# SCH_Color_Sensor_OPS_2021-07-07.net
KiCad netlist of a schematic drawn in EasyEDA
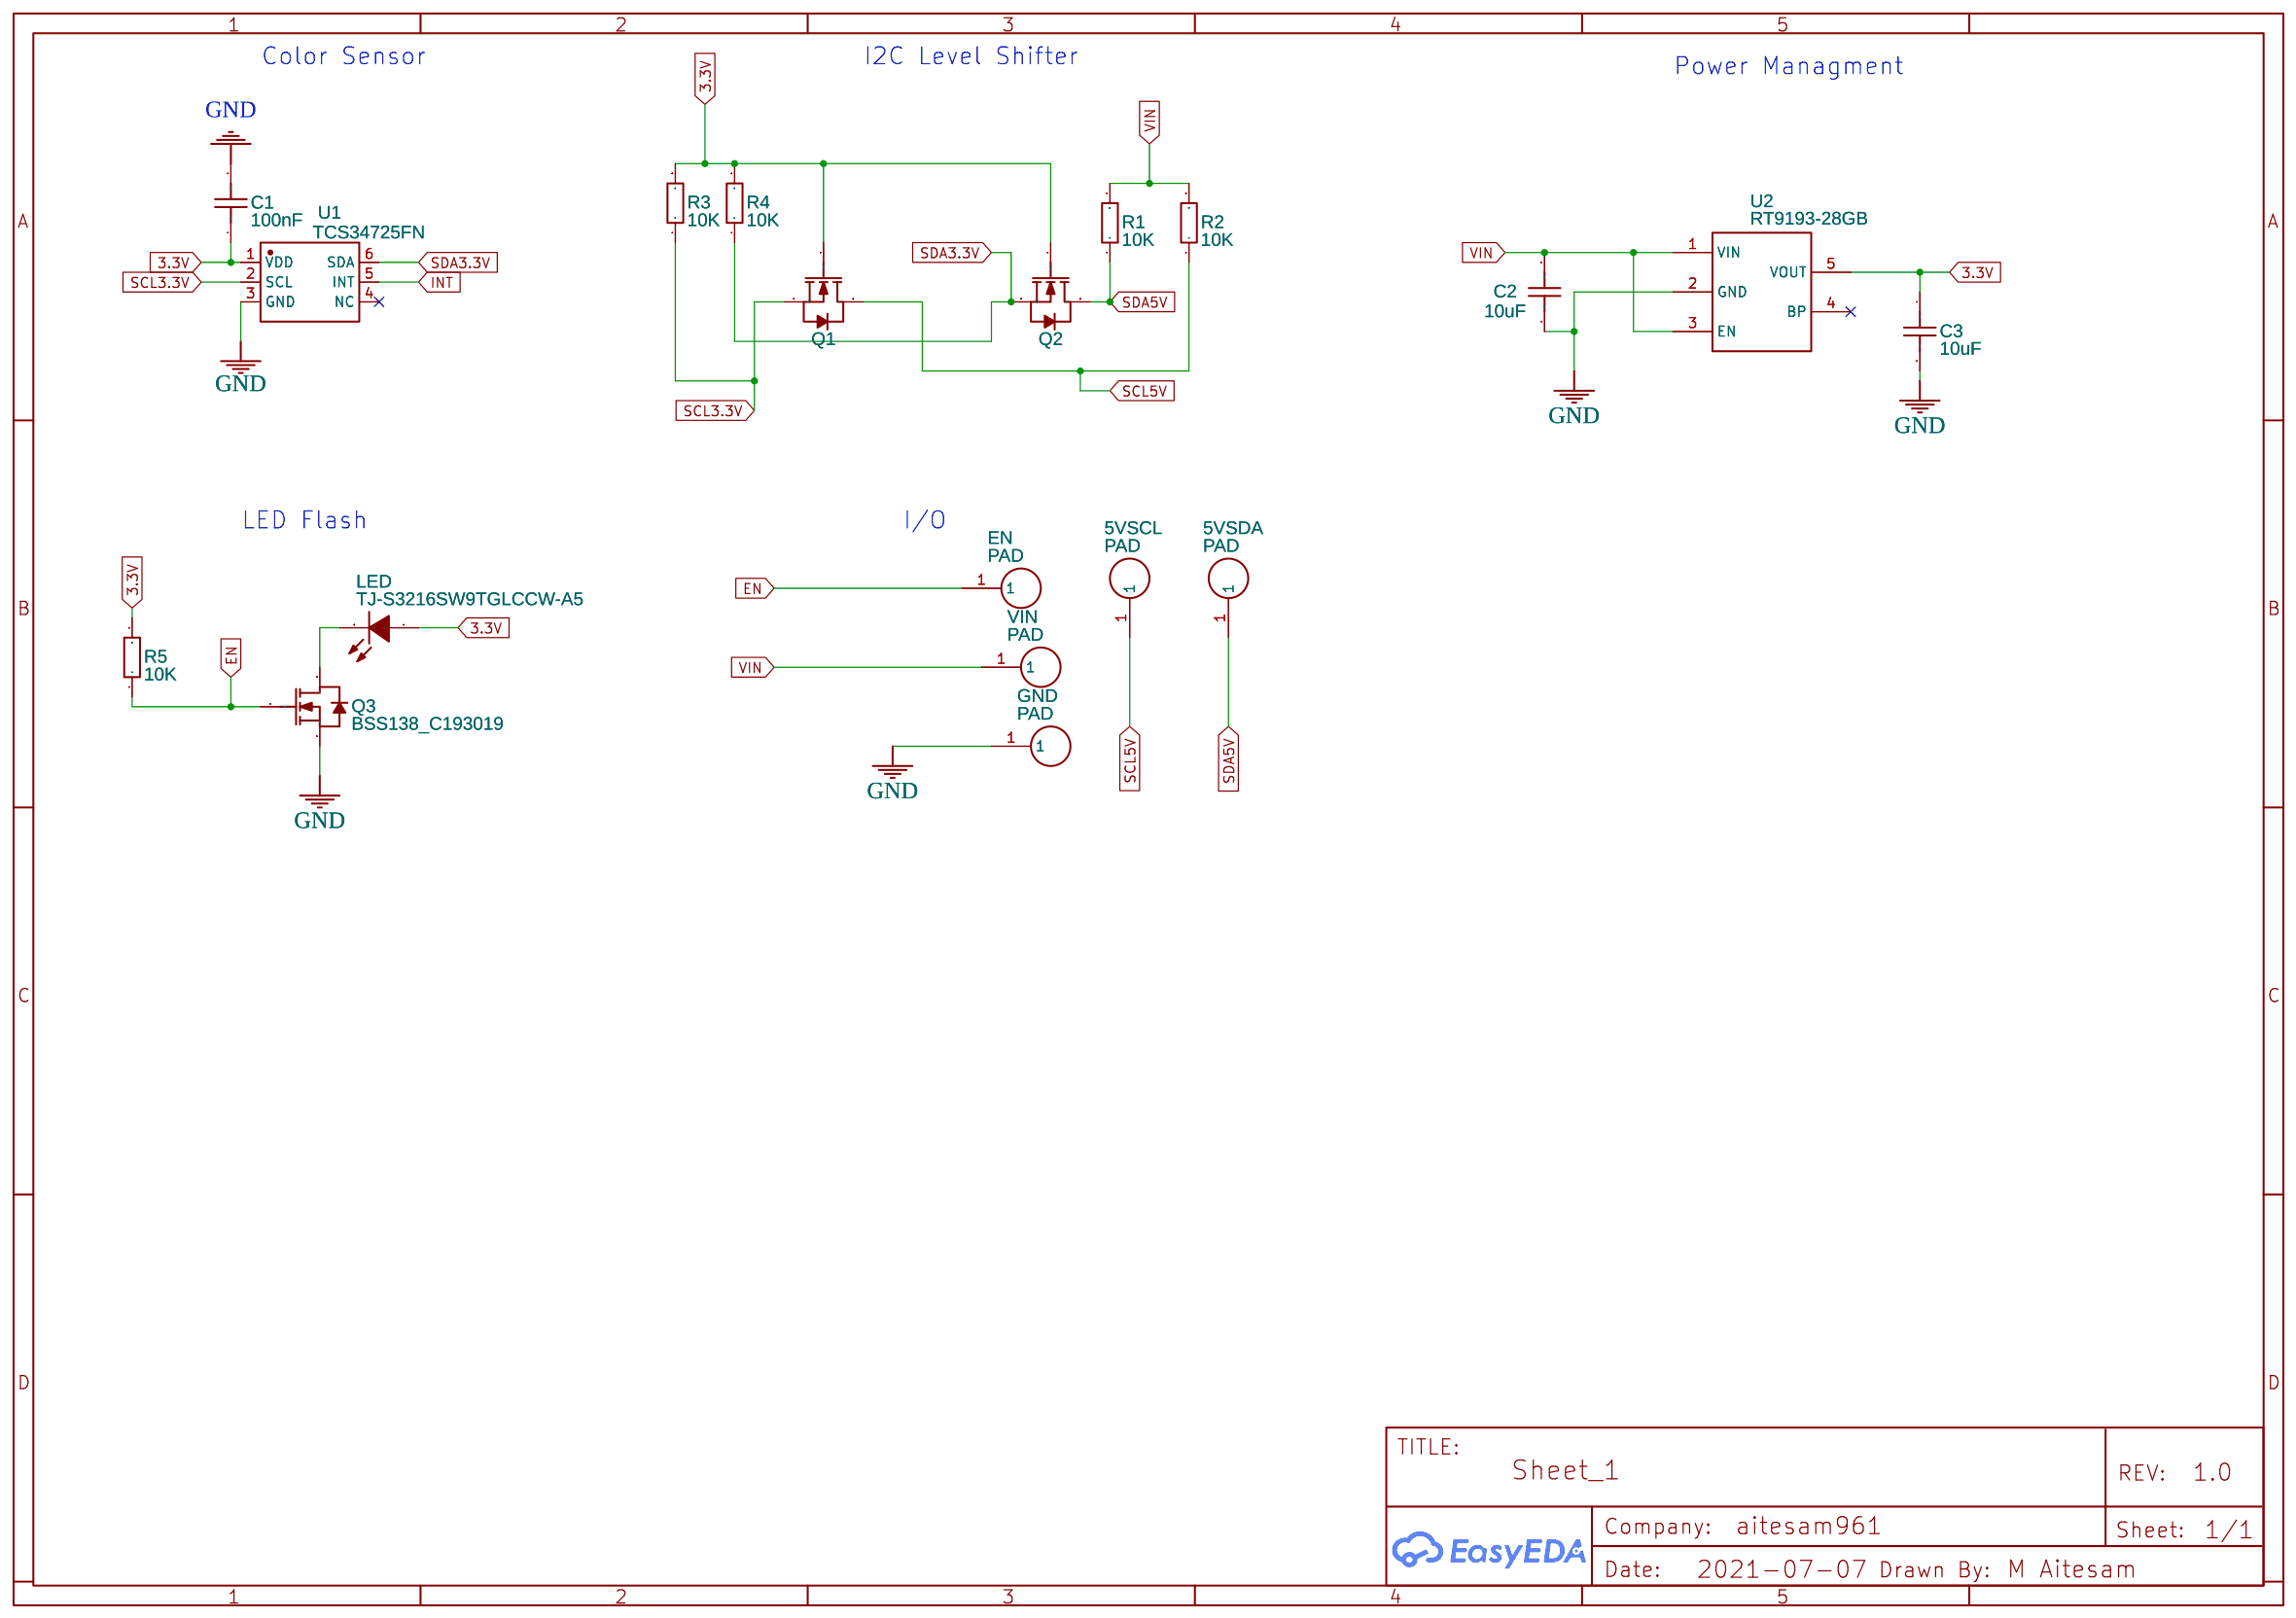
[diagram p0: schematic sheet]

(export (version "E")
  (design (tool "Eeschema 10.0.6"))
  (components
    (comp (ref "5VSCL") (value "PAD") (libsource (lib "") (part "PAD_2")))
    (comp (ref "5VSDA") (value "PAD") (libsource (lib "") (part "PAD_3")))
    (comp (ref "C1")
      (value "100nF")
      (fields
        (field (name "BOM_Manufacturer Part") "GCM155R71C104KA55D")
        (field (name "BOM_Supplier Part") "C85857")
      )
      (libsource (lib "") (part "GCM155R71C104KA55D"))
    )
    (comp (ref "C2")
      (value "10uF")
      (fields
        (field (name "BOM_Manufacturer Part") "CL10A106MQ8NNNC")
        (field (name "BOM_Supplier Part") "C1691")
      )
      (libsource (lib "") (part "CL10A106MQ8NNNC_1"))
    )
    (comp (ref "C3")
      (value "10uF")
      (fields
        (field (name "BOM_Manufacturer Part") "CL10A106MQ8NNNC")
        (field (name "BOM_Supplier Part") "C1691")
      )
      (libsource (lib "") (part "CL10A106MQ8NNNC"))
    )
    (comp (ref "EN") (value "PAD") (libsource (lib "") (part "PAD_4")))
    (comp (ref "GND") (value "PAD") (libsource (lib "") (part "PAD_1")))
    (comp (ref "LED")
      (value "TJ-S3216SW9TGLCCW-A5")
      (fields (field (name "BOM_Supplier Part") "C192680"))
      (libsource (lib "") (part "TJ-S3216SW9TGLCCW-A5"))
    )
    (comp (ref "Q1")
      (value "BSS138_C193019")
      (fields (field (name "BOM_Manufacturer Part") "BSS138") (field (name "BOM_Supplier Part") "C193019"))
      (libsource (lib "") (part "BSS138_C193019_1"))
    )
    (comp (ref "Q2")
      (value "BSS138_C193019")
      (fields (field (name "BOM_Manufacturer Part") "BSS138") (field (name "BOM_Supplier Part") "C193019"))
      (libsource (lib "") (part "BSS138_C193019_1"))
    )
    (comp (ref "Q3")
      (value "BSS138_C193019")
      (fields (field (name "BOM_Manufacturer Part") "BSS138") (field (name "BOM_Supplier Part") "C193019"))
      (libsource (lib "") (part "BSS138_C193019"))
    )
    (comp (ref "R1")
      (value "10K")
      (fields
        (field (name "BOM_Manufacturer Part") "0603WAJ0103T5E")
        (field (name "BOM_Supplier Part") "C15401")
      )
      (libsource (lib "") (part "0603WAJ0103T5E"))
    )
    (comp (ref "R2")
      (value "10K")
      (fields
        (field (name "BOM_Manufacturer Part") "0603WAJ0103T5E")
        (field (name "BOM_Supplier Part") "C15401")
      )
      (libsource (lib "") (part "0603WAJ0103T5E"))
    )
    (comp (ref "R3")
      (value "10K")
      (fields
        (field (name "BOM_Manufacturer Part") "0603WAJ0103T5E")
        (field (name "BOM_Supplier Part") "C15401")
      )
      (libsource (lib "") (part "0603WAJ0103T5E"))
    )
    (comp (ref "R4")
      (value "10K")
      (fields
        (field (name "BOM_Manufacturer Part") "0603WAJ0103T5E")
        (field (name "BOM_Supplier Part") "C15401")
      )
      (libsource (lib "") (part "0603WAJ0103T5E"))
    )
    (comp (ref "R5")
      (value "10K")
      (fields
        (field (name "BOM_Manufacturer Part") "0603WAJ0103T5E")
        (field (name "BOM_Supplier Part") "C15401")
      )
      (libsource (lib "") (part "0603WAJ0103T5E"))
    )
    (comp (ref "U1")
      (value "TCS34725FN")
      (fields (field (name "BOM_Supplier Part") "C2649487"))
      (libsource (lib "") (part "TCS34725FN"))
    )
    (comp (ref "U2")
      (value "RT9193-28GB")
      (fields (field (name "BOM_Supplier Part") "C56731"))
      (libsource (lib "") (part "RT9193-28GB"))
    )
    (comp (ref "VIN") (value "PAD") (libsource (lib "") (part "PAD")))
  )
  (nets
    (net (code "1") (name "3.3V") (class "Default")
      (node (ref "C1") (pin "1") (pinfunction "1_1") (pintype "unspecified"))
      (node (ref "C3") (pin "1") (pinfunction "1_1") (pintype "unspecified"))
      (node (ref "LED") (pin "1") (pinfunction "A_1") (pintype "unspecified"))
      (node (ref "Q1") (pin "1") (pinfunction "G_1") (pintype "unspecified"))
      (node (ref "Q2") (pin "1") (pinfunction "G_1") (pintype "unspecified"))
      (node (ref "R3") (pin "2") (pinfunction "2_2") (pintype "input"))
      (node (ref "R4") (pin "2") (pinfunction "2_2") (pintype "input"))
      (node (ref "R5") (pin "2") (pinfunction "2_2") (pintype "input"))
      (node (ref "U1") (pin "1") (pinfunction "VDD_1") (pintype "unspecified"))
      (node (ref "U2") (pin "5") (pinfunction "VOUT_5") (pintype "unspecified"))
    )
    (net (code "2") (name "EN") (class "Default")
      (node (ref "EN") (pin "1") (pinfunction "1_1") (pintype "unspecified"))
      (node (ref "Q3") (pin "1") (pinfunction "G_1") (pintype "unspecified"))
      (node (ref "R5") (pin "1") (pinfunction "1_1") (pintype "input"))
    )
    (net (code "3") (name "GND") (class "Default")
      (node (ref "C1") (pin "2") (pinfunction "2_2") (pintype "unspecified"))
      (node (ref "C2") (pin "1") (pinfunction "1_1") (pintype "unspecified"))
      (node (ref "C3") (pin "2") (pinfunction "2_2") (pintype "unspecified"))
      (node (ref "GND") (pin "1") (pinfunction "1_1") (pintype "unspecified"))
      (node (ref "Q3") (pin "2") (pinfunction "S_2") (pintype "unspecified"))
      (node (ref "U1") (pin "3") (pinfunction "GND_3") (pintype "unspecified"))
      (node (ref "U2") (pin "2") (pinfunction "GND_2") (pintype "unspecified"))
    )
    (net (code "4") (name "INT") (class "Default")
      (node (ref "U1") (pin "5") (pinfunction "INT_5") (pintype "unspecified"))
    )
    (net (code "5") (name "Net-(LED-K)") (class "Default")
      (node (ref "LED") (pin "2") (pinfunction "K_2") (pintype "unspecified"))
      (node (ref "Q3") (pin "3") (pinfunction "D_3") (pintype "unspecified"))
    )
    (net (code "6") (name "SCL3.3V") (class "Default")
      (node (ref "Q1") (pin "2") (pinfunction "S_2") (pintype "unspecified"))
      (node (ref "R3") (pin "1") (pinfunction "1_1") (pintype "input"))
      (node (ref "U1") (pin "2") (pinfunction "SCL_2") (pintype "unspecified"))
    )
    (net (code "7") (name "SCL5V") (class "Default")
      (node (ref "5VSCL") (pin "1") (pinfunction "1_1") (pintype "unspecified"))
      (node (ref "Q1") (pin "3") (pinfunction "D_3") (pintype "unspecified"))
      (node (ref "R2") (pin "1") (pinfunction "1_1") (pintype "input"))
    )
    (net (code "8") (name "SDA3.3V") (class "Default")
      (node (ref "Q2") (pin "2") (pinfunction "S_2") (pintype "unspecified"))
      (node (ref "R4") (pin "1") (pinfunction "1_1") (pintype "input"))
      (node (ref "U1") (pin "6") (pinfunction "SDA_6") (pintype "unspecified"))
    )
    (net (code "9") (name "SDA5V") (class "Default")
      (node (ref "5VSDA") (pin "1") (pinfunction "1_1") (pintype "unspecified"))
      (node (ref "Q2") (pin "3") (pinfunction "D_3") (pintype "unspecified"))
      (node (ref "R1") (pin "1") (pinfunction "1_1") (pintype "input"))
    )
    (net (code "10") (name "VIN") (class "Default")
      (node (ref "C2") (pin "2") (pinfunction "2_2") (pintype "unspecified"))
      (node (ref "R1") (pin "2") (pinfunction "2_2") (pintype "input"))
      (node (ref "R2") (pin "2") (pinfunction "2_2") (pintype "input"))
      (node (ref "U2") (pin "1") (pinfunction "VIN_1") (pintype "unspecified"))
      (node (ref "U2") (pin "3") (pinfunction "EN_3") (pintype "unspecified"))
      (node (ref "VIN") (pin "1") (pinfunction "1_1") (pintype "unspecified"))
    )
    (net (code "11") (name "unconnected-(U1-NC-Pad4)") (class "Default")
      (node (ref "U1") (pin "4") (pinfunction "NC_4") (pintype "unspecified+no_connect"))
    )
    (net (code "12") (name "unconnected-(U2-BP-Pad4)") (class "Default")
      (node (ref "U2") (pin "4") (pinfunction "BP_4") (pintype "unspecified+no_connect"))
    )
  )
)
